# Recupera_ao_e_Paraquedas.net
KiCad netlist of a schematic drawn in EAGLE
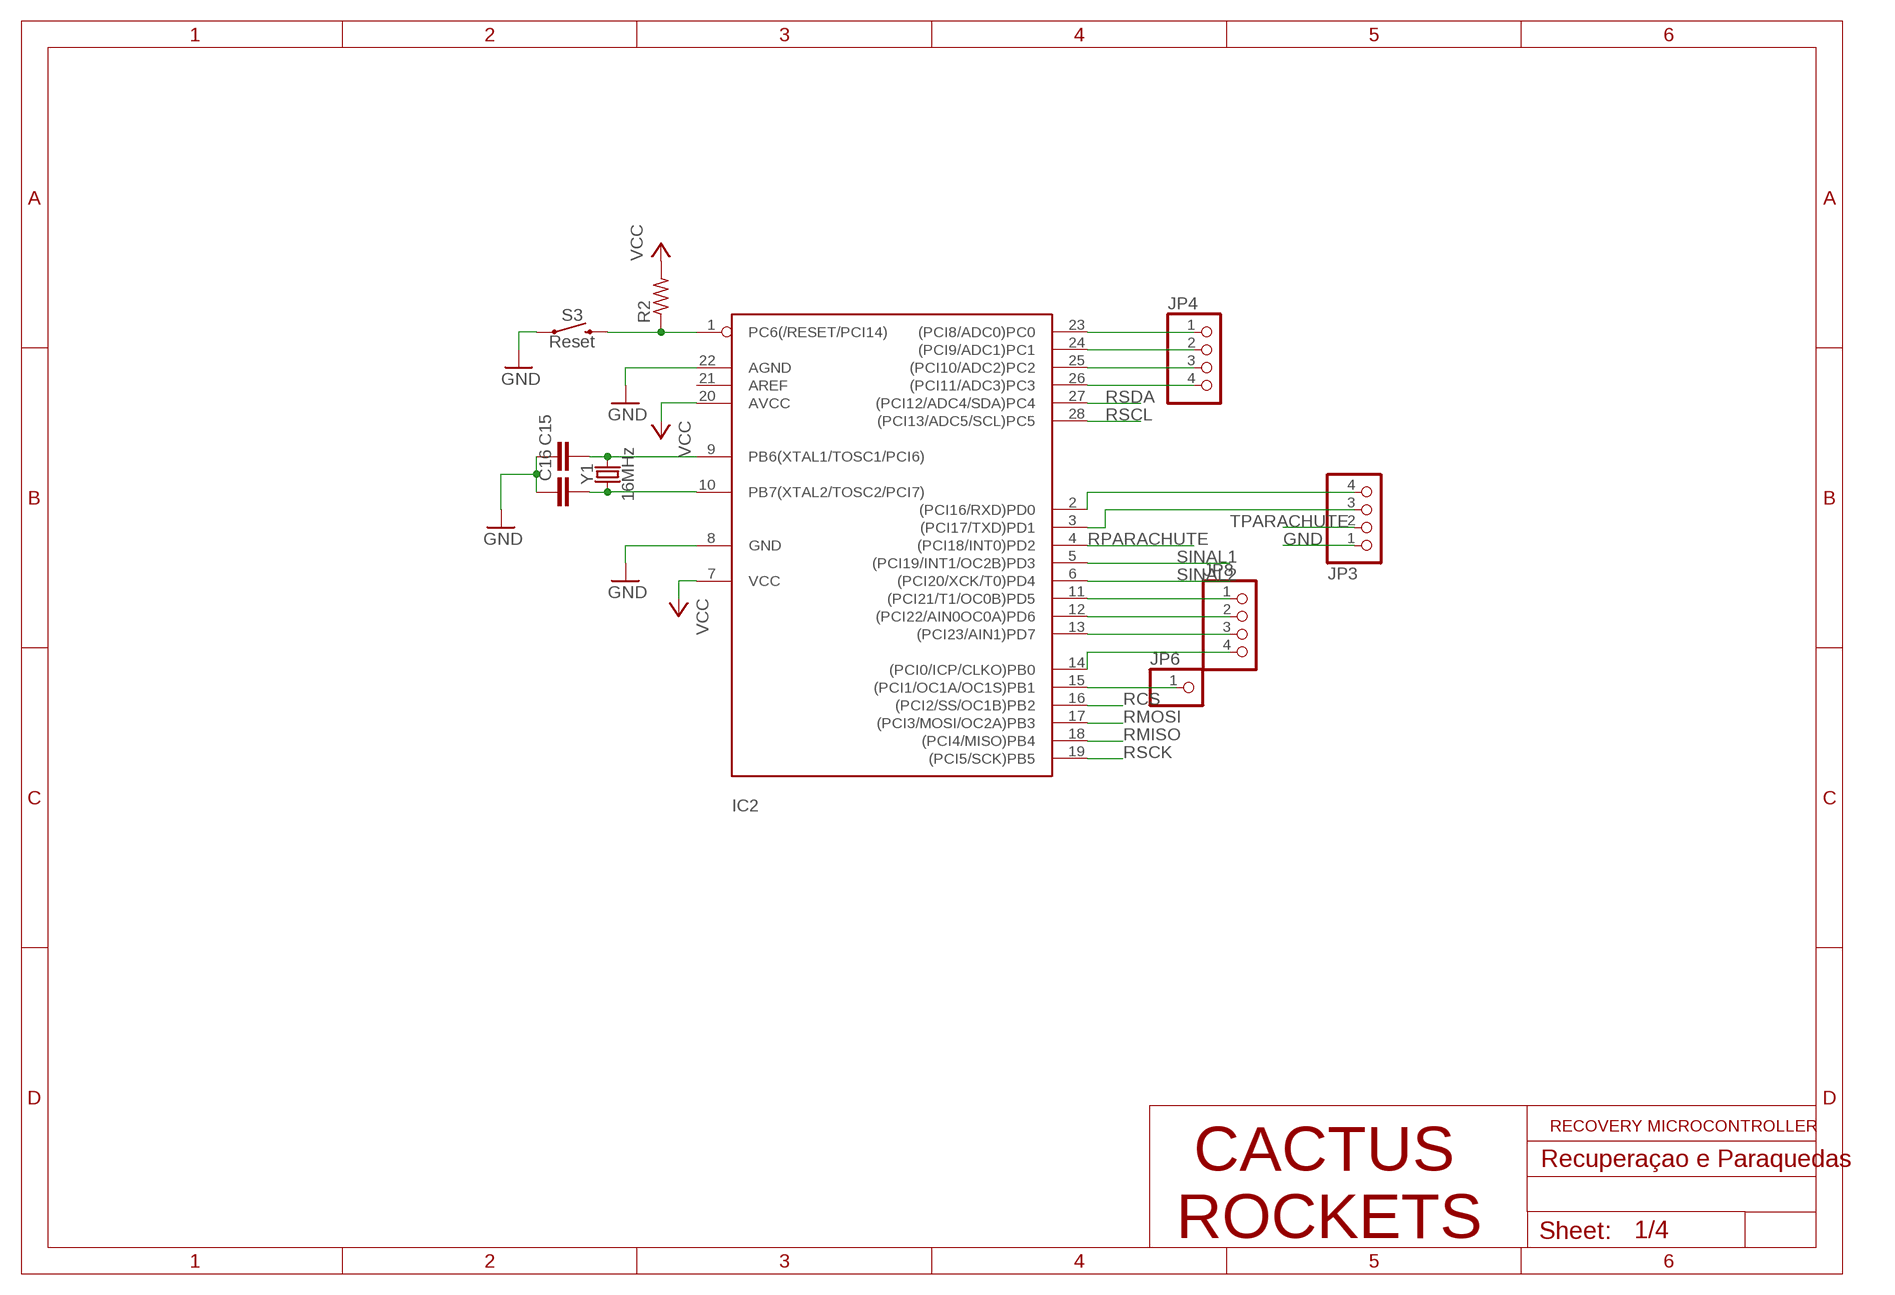
[diagram p0: schematic, sheet 1]
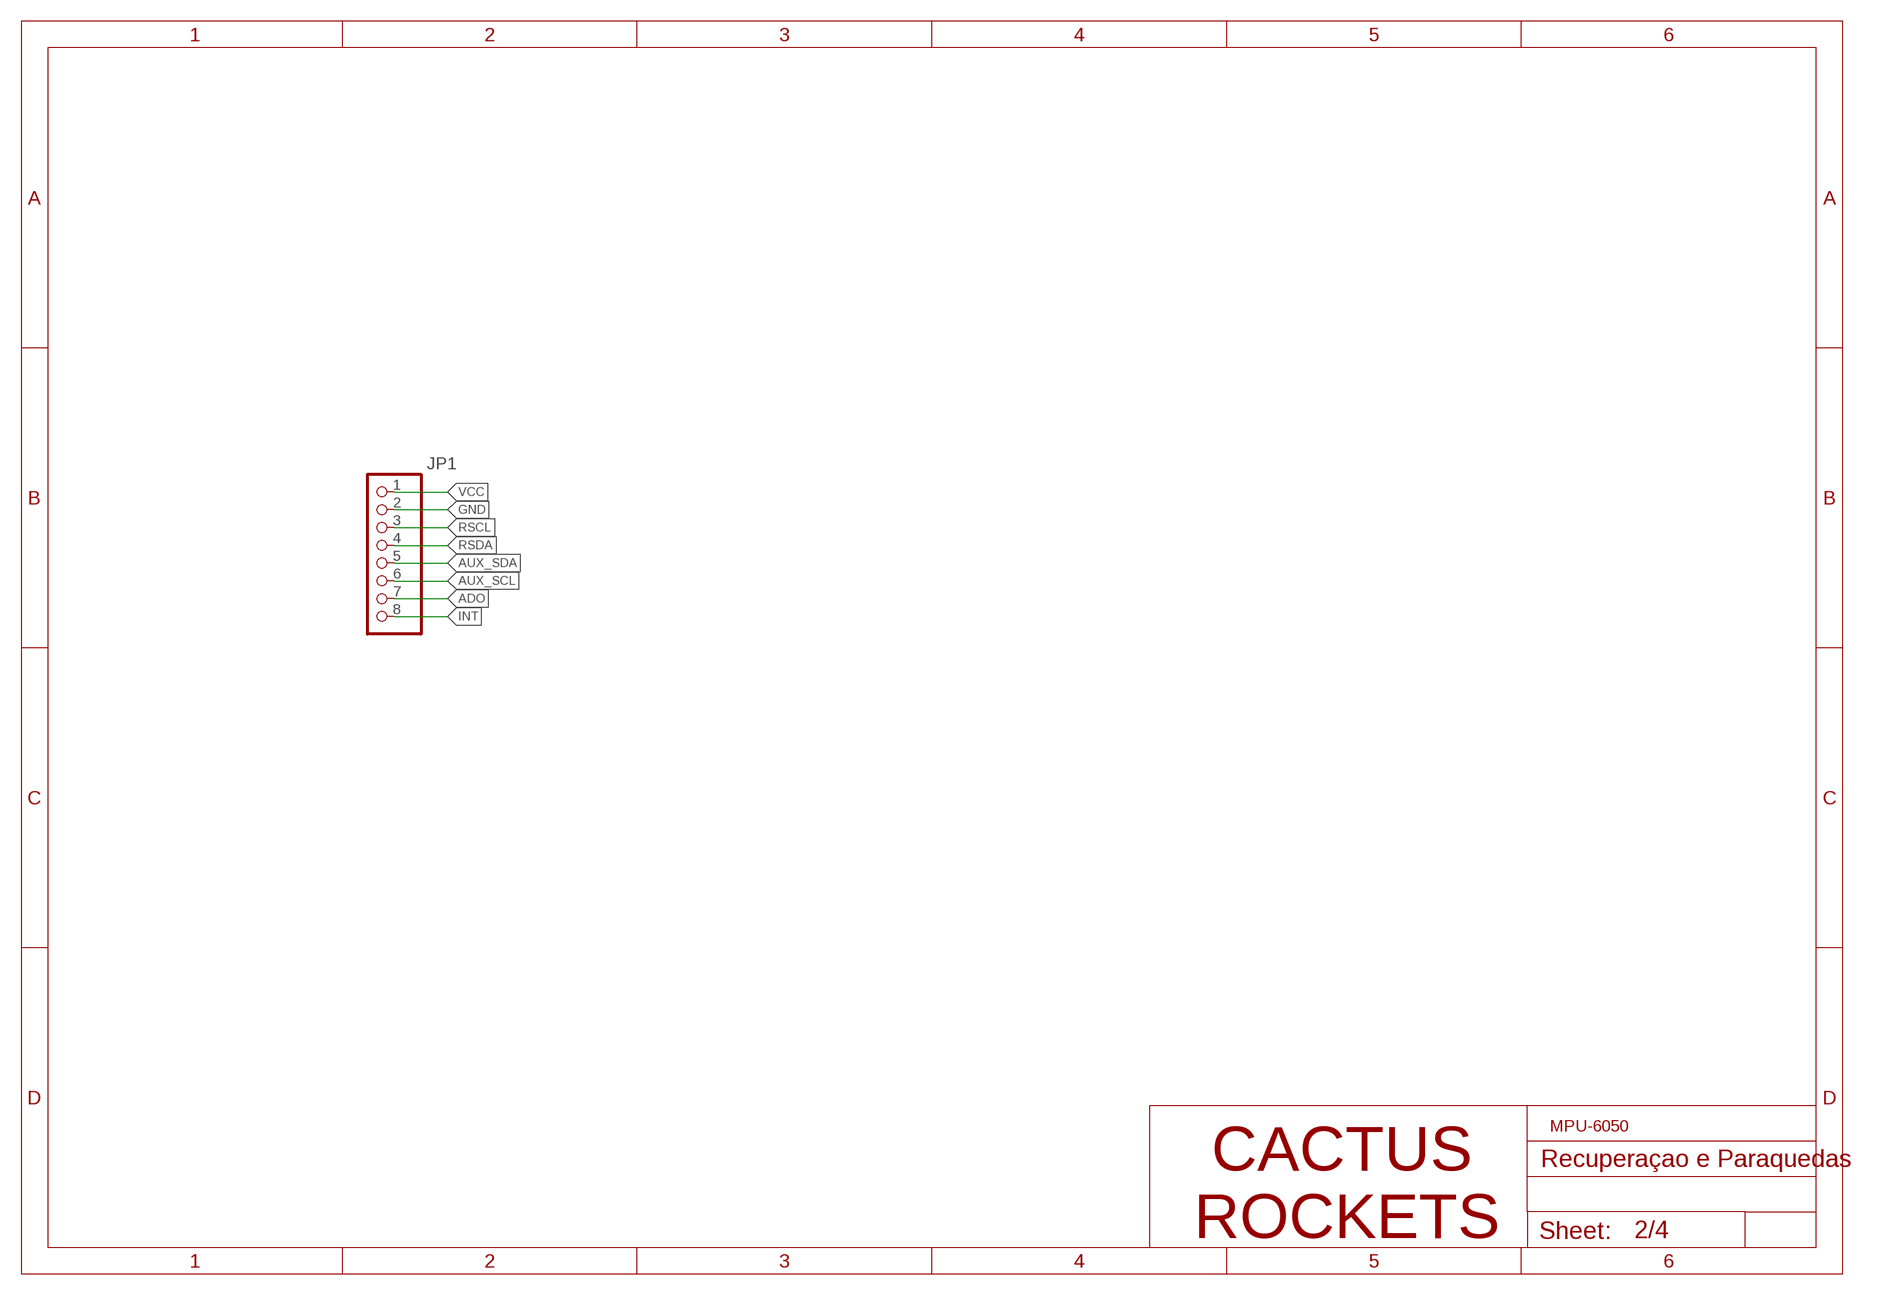
[diagram p1: schematic, sheet 2]
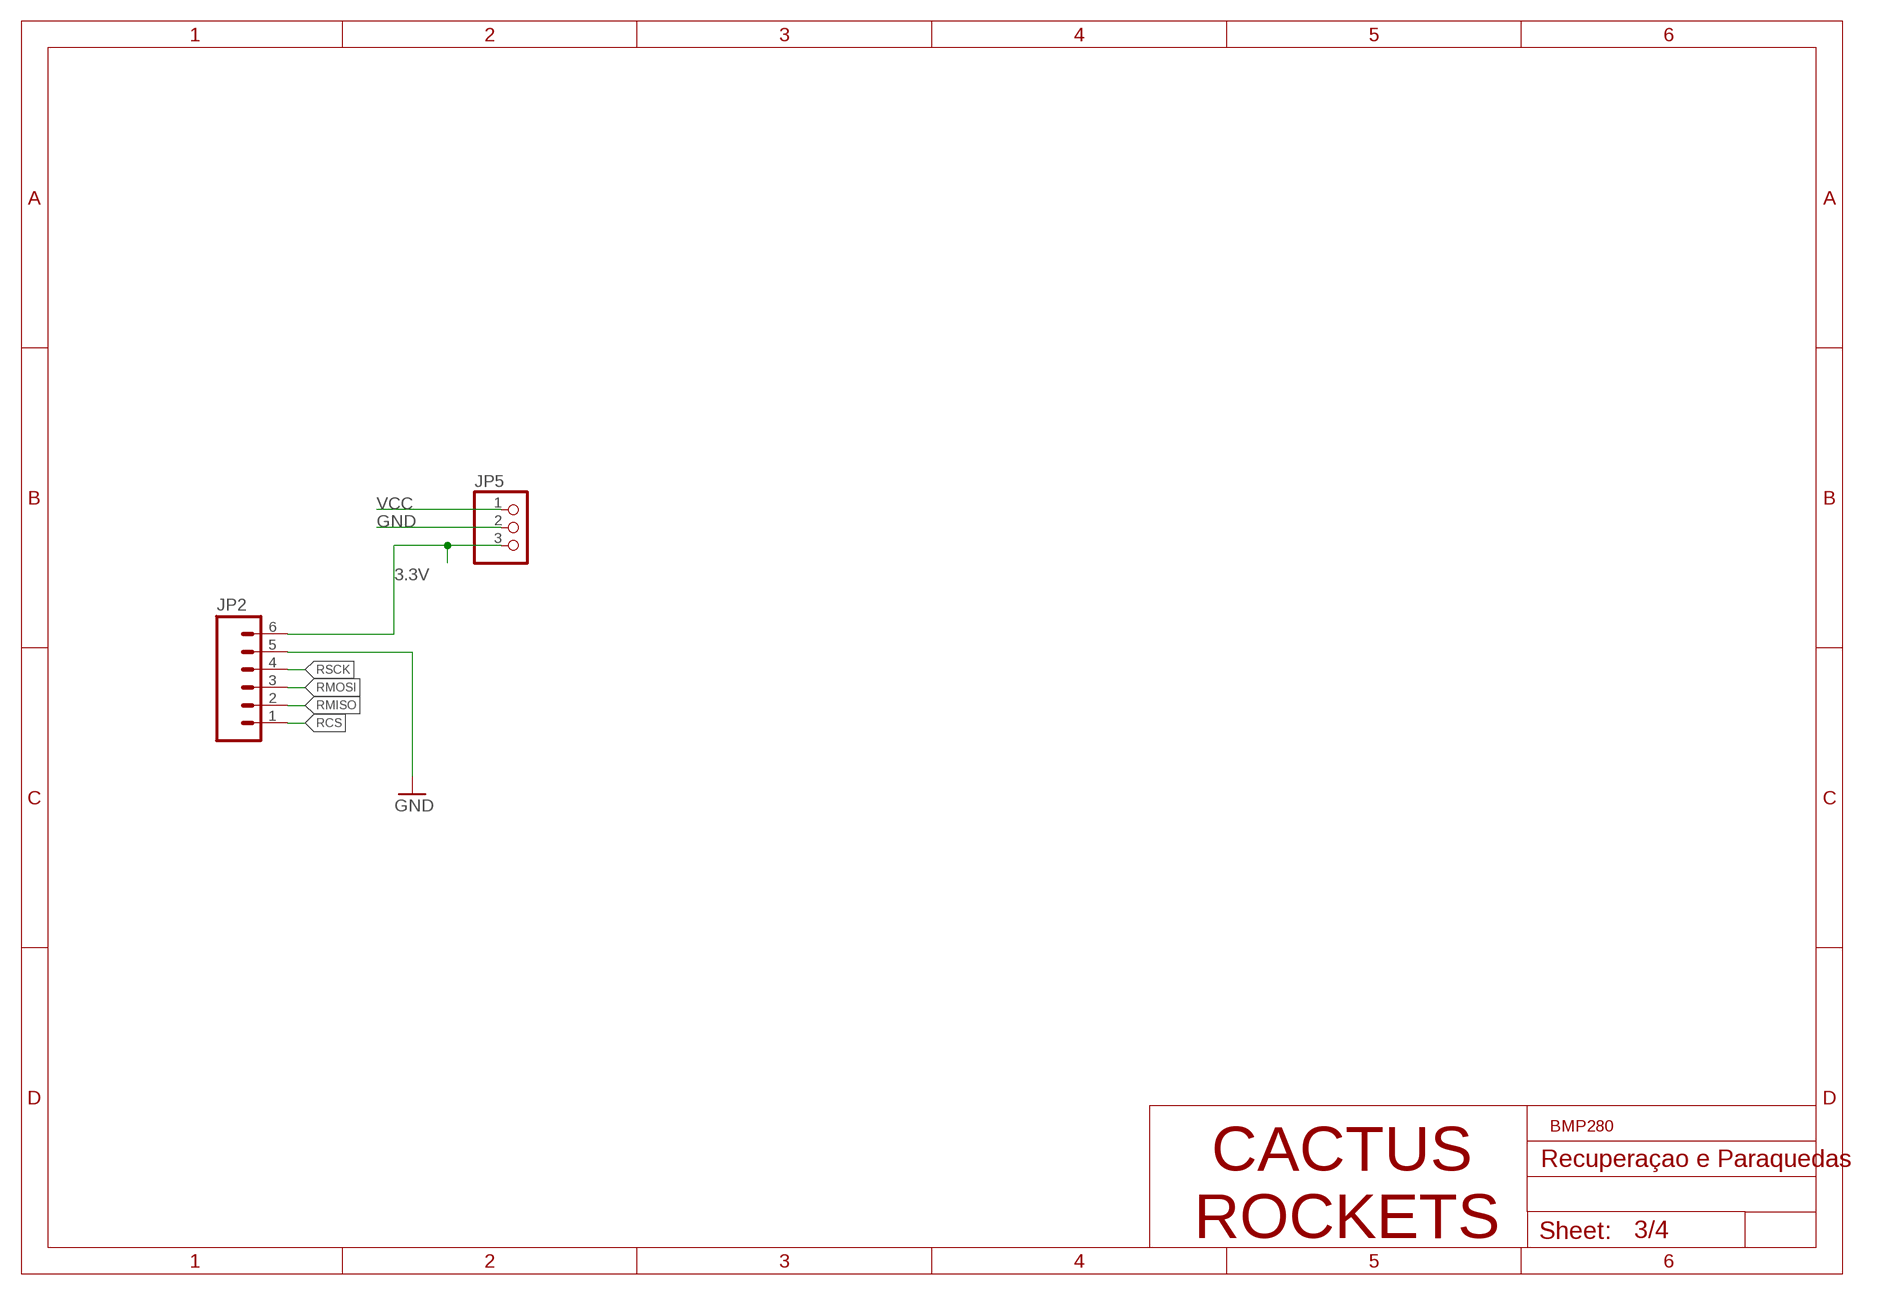
[diagram p2: schematic, sheet 3]
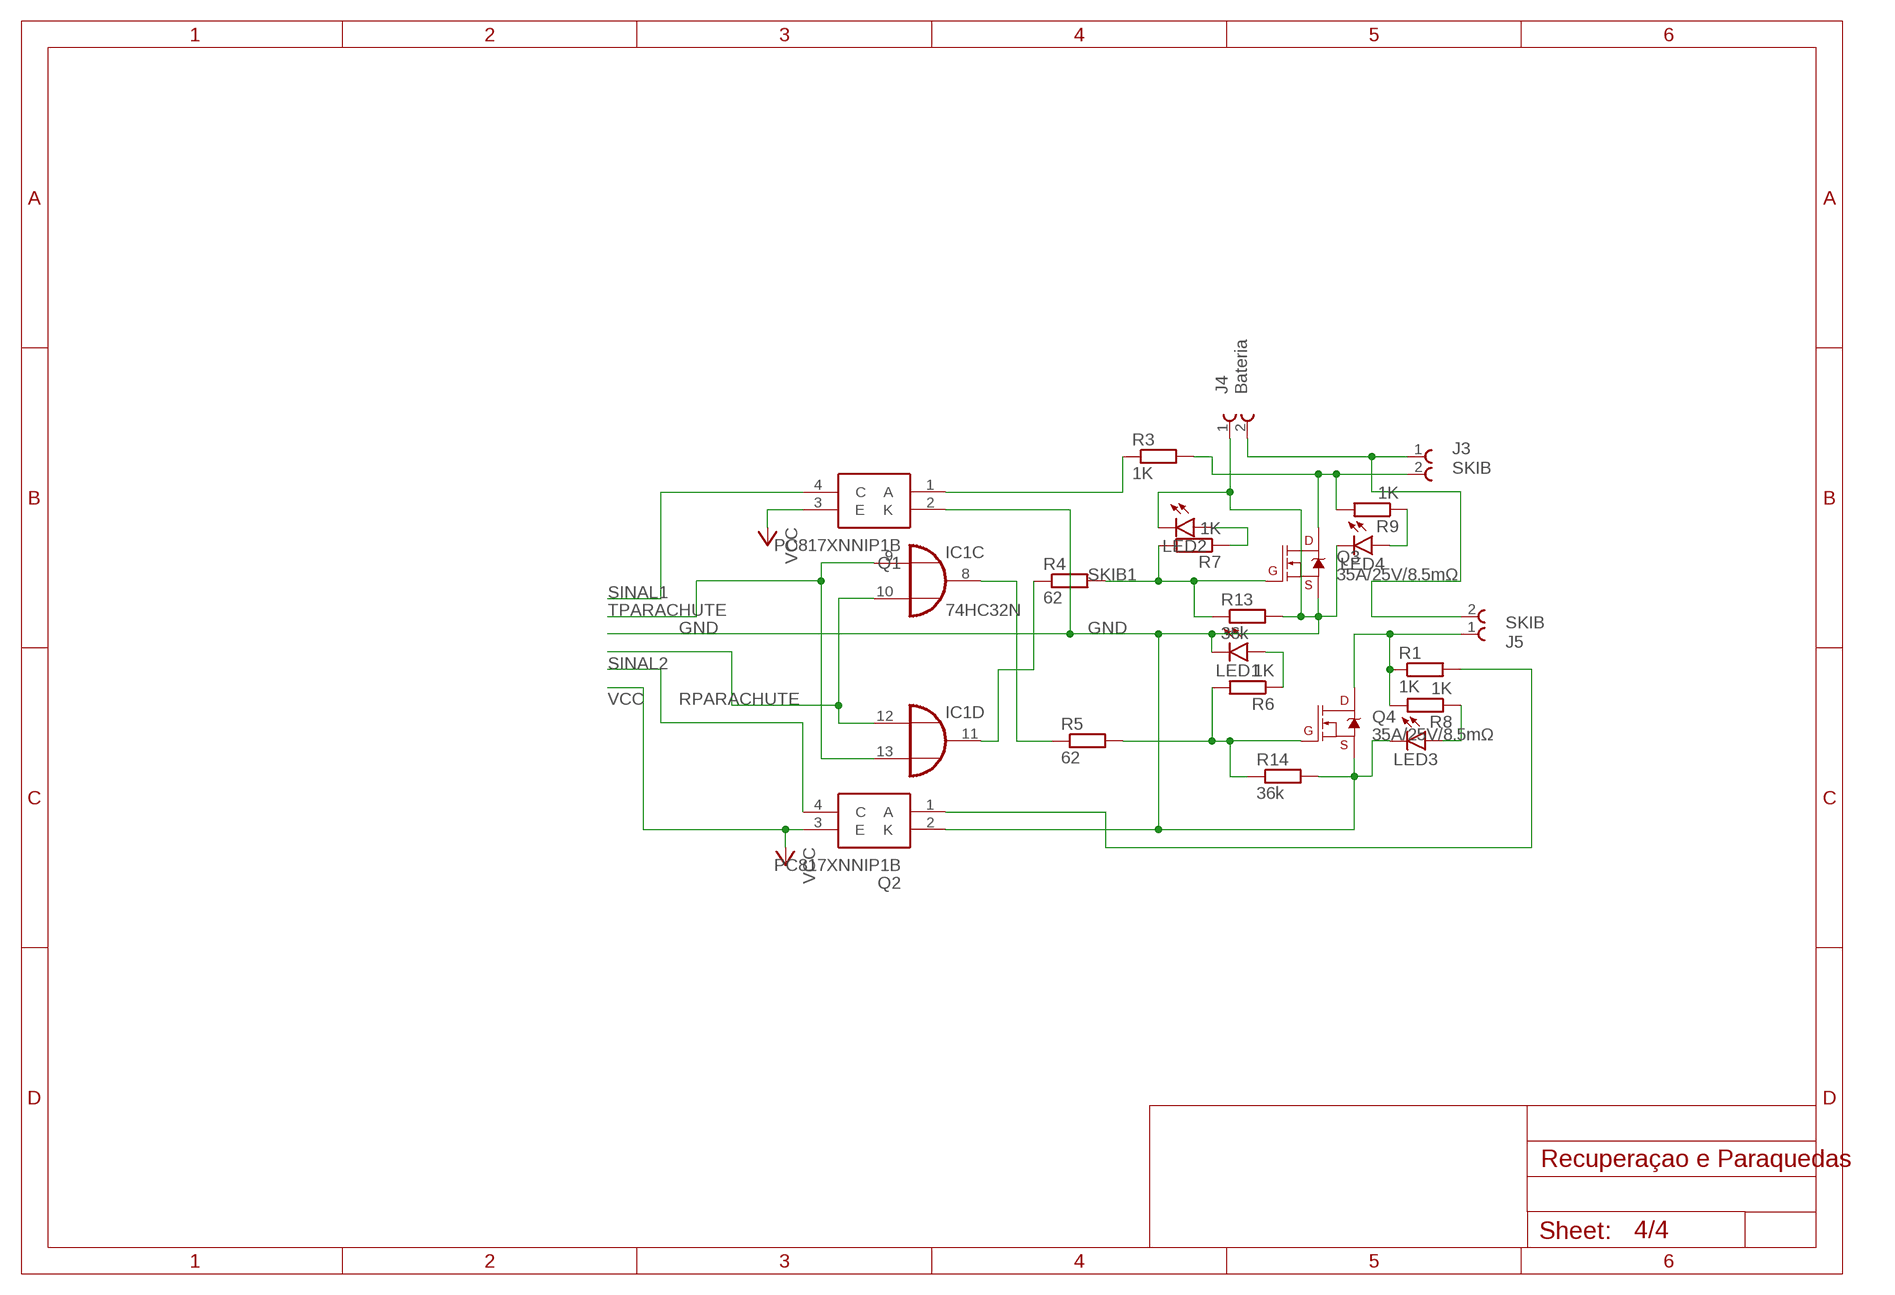
[diagram p3: schematic, sheet 4]

(export (version "E")
  (design (tool "Eeschema 10.0.6"))
  (components
    (comp (ref "JP1")
      (value "PINHD-1X8")
      (footprint "eagle-import:1X08")
      (libsource (lib "eagle-import") (part "PINHD-1X8"))
    )
    (comp (ref "JP2")
      (value "M06NO_SILK_FEMALE_PTH")
      (footprint "eagle-import:1X06_NO_SILK")
      (libsource (lib "eagle-import") (part "M06NO_SILK_FEMALE_PTH"))
    )
    (comp (ref "JP5")
      (value "PINHD-1X3/90")
      (footprint "eagle-import:1X03_90")
      (libsource (lib "eagle-import") (part "PINHD-1X3/90"))
    )
    (comp (ref "C15")
      (value "C-EU025-025X050")
      (footprint "eagle-import:C025-025X050")
      (libsource (lib "eagle-import") (part "C-EU025-025X050"))
    )
    (comp (ref "C16")
      (value "C-EU025-025X050")
      (footprint "eagle-import:C025-025X050")
      (libsource (lib "eagle-import") (part "C-EU025-025X050"))
    )
    (comp (ref "IC2")
      (value "ATMEGA328-20P")
      (footprint "eagle-import:DIL28-3")
      (libsource (lib "eagle-import") (part "ATMEGA328P-20"))
    )
    (comp (ref "JP3")
      (value "PINHD-1X4/90")
      (footprint "eagle-import:1X04_90")
      (libsource (lib "eagle-import") (part "PINHD-1X4/90"))
    )
    (comp (ref "JP4")
      (value "PINHD-1X4")
      (footprint "eagle-import:1X04")
      (libsource (lib "eagle-import") (part "PINHD-1X4"))
    )
    (comp (ref "JP6")
      (value "PINHD-1X1")
      (footprint "eagle-import:1X01")
      (libsource (lib "eagle-import") (part "PINHD-1X1"))
    )
    (comp (ref "JP8")
      (value "PINHD-1X4")
      (footprint "eagle-import:1X04")
      (libsource (lib "eagle-import") (part "PINHD-1X4"))
    )
    (comp (ref "R2")
      (value "R-US_0207/10")
      (footprint "eagle-import:0207_10")
      (libsource (lib "eagle-import") (part "R-US_0207/10"))
    )
    (comp (ref "S3")
      (value "Reset")
      (footprint "eagle-import:TACTILE_SWITCH_PTH_6.0MM")
      (libsource (lib "eagle-import") (part "MOMENTARY-SWITCH-SPST-PTH-6.0MM"))
    )
    (comp (ref "Y1")
      (value "16MHz")
      (footprint "eagle-import:HC49US")
      (libsource (lib "eagle-import") (part "CRYSTAL-16MHZPTH-HC49US"))
    )
    (comp (ref "IC1")
      (value "74HC32N")
      (footprint "eagle-import:DIL14")
      (libsource (lib "eagle-import") (part "7432NHC"))
    )
    (comp (ref "J3")
      (value "SKIB")
      (footprint "eagle-import:691111710002")
      (fields (field (name "MF") "Wurth Electronics") (field (name "MP") "691111710002"))
      (libsource (lib "eagle-import") (part "691111710002"))
    )
    (comp (ref "J4")
      (value "Bateria")
      (footprint "eagle-import:691111710002")
      (fields (field (name "MF") "Wurth Electronics") (field (name "MP") "691111710002"))
      (libsource (lib "eagle-import") (part "691111710002"))
    )
    (comp (ref "J5")
      (value "SKIB")
      (footprint "eagle-import:691111710002")
      (fields (field (name "MF") "Wurth Electronics") (field (name "MP") "691111710002"))
      (libsource (lib "eagle-import") (part "691111710002"))
    )
    (comp (ref "LED1")
      (value "LEDCHIP-LED0805")
      (footprint "eagle-import:CHIP-LED0805")
      (libsource (lib "eagle-import") (part "LEDCHIP-LED0805"))
    )
    (comp (ref "LED2")
      (value "LEDCHIP-LED0805")
      (footprint "eagle-import:CHIP-LED0805")
      (libsource (lib "eagle-import") (part "LEDCHIP-LED0805"))
    )
    (comp (ref "LED3")
      (value "LEDCHIP-LED0805")
      (footprint "eagle-import:CHIP-LED0805")
      (libsource (lib "eagle-import") (part "LEDCHIP-LED0805"))
    )
    (comp (ref "LED4")
      (value "LEDCHIP-LED0805")
      (footprint "eagle-import:CHIP-LED0805")
      (libsource (lib "eagle-import") (part "LEDCHIP-LED0805"))
    )
    (comp (ref "Q1")
      (value "PC817XNNIP1B")
      (footprint "eagle-import:SOP254P960X420-4N")
      (fields (field (name "MOUSER_PART_NUMBER") "852-PC817XNNIP1B"))
      (libsource (lib "eagle-import") (part "PC817XNNIP1B"))
    )
    (comp (ref "Q2")
      (value "PC817XNNIP1B")
      (footprint "eagle-import:SOP254P960X420-4N")
      (fields (field (name "MOUSER_PART_NUMBER") "852-PC817XNNIP1B"))
      (libsource (lib "eagle-import") (part "PC817XNNIP1B"))
    )
    (comp (ref "Q3")
      (value "35A/25V/8.5mΩ")
      (footprint "eagle-import:TO-252_DPAK")
      (libsource (lib "eagle-import") (part "MOSFET-NCH-FDD8780"))
    )
    (comp (ref "Q4")
      (value "35A/25V/8.5mΩ")
      (footprint "eagle-import:TO-252_DPAK")
      (libsource (lib "eagle-import") (part "MOSFET-NCH-FDD8780"))
    )
    (comp (ref "R1")
      (value "1K")
      (footprint "eagle-import:R0603")
      (libsource (lib "eagle-import") (part "R-EU_R0603"))
    )
    (comp (ref "R3")
      (value "1K")
      (footprint "eagle-import:R0603")
      (libsource (lib "eagle-import") (part "R-EU_R0603"))
    )
    (comp (ref "R4")
      (value "62")
      (footprint "eagle-import:M0805")
      (libsource (lib "eagle-import") (part "R-EU_M0805"))
    )
    (comp (ref "R5")
      (value "62")
      (footprint "eagle-import:M0805")
      (libsource (lib "eagle-import") (part "R-EU_M0805"))
    )
    (comp (ref "R6")
      (value "1K")
      (footprint "eagle-import:M0805")
      (libsource (lib "eagle-import") (part "R-EU_M0805"))
    )
    (comp (ref "R7")
      (value "1K")
      (footprint "eagle-import:M0805")
      (libsource (lib "eagle-import") (part "R-EU_M0805"))
    )
    (comp (ref "R8")
      (value "1K")
      (footprint "eagle-import:M0805")
      (libsource (lib "eagle-import") (part "R-EU_M0805"))
    )
    (comp (ref "R9")
      (value "1K")
      (footprint "eagle-import:M0805")
      (libsource (lib "eagle-import") (part "R-EU_M0805"))
    )
    (comp (ref "R13")
      (value "36k")
      (footprint "eagle-import:M0805")
      (libsource (lib "eagle-import") (part "R-EU_M0805"))
    )
    (comp (ref "R14")
      (value "36k")
      (footprint "eagle-import:M0805")
      (libsource (lib "eagle-import") (part "R-EU_M0805"))
    )
  )
  (nets
    (net (code "1") (name "3.3V") (class "Default")
      (node (ref "JP2") (pin "6") (pinfunction "6_6") (pintype "passive"))
      (node (ref "JP5") (pin "3") (pinfunction "3_3") (pintype "passive"))
    )
    (net (code "2") (name "ADO") (class "Default")
      (node (ref "JP1") (pin "7") (pinfunction "7_7") (pintype "passive"))
    )
    (net (code "3") (name "AUX_SCL") (class "Default")
      (node (ref "JP1") (pin "6") (pinfunction "6_6") (pintype "passive"))
    )
    (net (code "4") (name "AUX_SDA") (class "Default")
      (node (ref "JP1") (pin "5") (pinfunction "5_5") (pintype "passive"))
    )
    (net (code "5") (name "GND") (class "Default")
      (node (ref "C15") (pin "1") (pinfunction "1_1") (pintype "passive"))
      (node (ref "C16") (pin "1") (pinfunction "1_1") (pintype "passive"))
      (node (ref "IC2") (pin "22") (pinfunction "AGND_22") (pintype "bidirectional"))
      (node (ref "IC2") (pin "8") (pinfunction "GND_8") (pintype "bidirectional"))
      (node (ref "J4") (pin "1") (pinfunction "1_1") (pintype "passive"))
      (node (ref "JP1") (pin "2") (pinfunction "2_2") (pintype "passive"))
      (node (ref "JP2") (pin "5") (pinfunction "5_5") (pintype "passive"))
      (node (ref "JP3") (pin "1") (pinfunction "1_1") (pintype "passive"))
      (node (ref "JP5") (pin "2") (pinfunction "2_2") (pintype "passive"))
      (node (ref "LED1") (pin "C") (pinfunction "C_C") (pintype "passive"))
      (node (ref "LED2") (pin "C") (pinfunction "C_C") (pintype "passive"))
      (node (ref "LED3") (pin "C") (pinfunction "C_C") (pintype "passive"))
      (node (ref "LED4") (pin "C") (pinfunction "C_C") (pintype "passive"))
      (node (ref "Q1") (pin "2") (pinfunction "K_2") (pintype "bidirectional"))
      (node (ref "Q2") (pin "2") (pinfunction "K_2") (pintype "bidirectional"))
      (node (ref "Q3") (pin "3") (pinfunction "S_3") (pintype "bidirectional"))
      (node (ref "Q4") (pin "3") (pinfunction "S_3") (pintype "bidirectional"))
      (node (ref "R13") (pin "2") (pinfunction "2_2") (pintype "passive"))
      (node (ref "R14") (pin "2") (pinfunction "2_2") (pintype "passive"))
      (node (ref "S3") (pin "1") (pinfunction "1_1") (pintype "passive"))
      (node (ref "S3") (pin "2") (pinfunction "1_2") (pintype "passive"))
    )
    (net (code "6") (name "INT") (class "Default")
      (node (ref "JP1") (pin "8") (pinfunction "8_8") (pintype "passive"))
    )
    (net (code "7") (name "Net-(IC1C-O)") (class "Default")
      (node (ref "IC1") (pin "8") (pinfunction "O_8") (pintype "output"))
      (node (ref "R5") (pin "1") (pinfunction "1_1") (pintype "passive"))
    )
    (net (code "8") (name "Net-(IC1D-O)") (class "Default")
      (node (ref "IC1") (pin "11") (pinfunction "O_11") (pintype "output"))
      (node (ref "R4") (pin "1") (pinfunction "1_1") (pintype "passive"))
    )
    (net (code "9") (name "Net-(IC2-(PCI0{slash}ICP{slash}CLKO)PB0)") (class "Default")
      (node (ref "IC2") (pin "14") (pinfunction "(PCI0/ICP/CLKO)PB0_14") (pintype "bidirectional"))
      (node (ref "JP8") (pin "4") (pinfunction "4_4") (pintype "passive"))
    )
    (net (code "10") (name "Net-(IC2-(PCI1{slash}OC1A{slash}OC1S)PB1)") (class "Default")
      (node (ref "IC2") (pin "15") (pinfunction "(PCI1/OC1A/OC1S)PB1_15") (pintype "bidirectional"))
      (node (ref "JP6") (pin "1") (pinfunction "1_1") (pintype "passive"))
    )
    (net (code "11") (name "Net-(IC2-(PCI8{slash}ADC0)PC0)") (class "Default")
      (node (ref "IC2") (pin "23") (pinfunction "(PCI8/ADC0)PC0_23") (pintype "bidirectional"))
      (node (ref "JP4") (pin "1") (pinfunction "1_1") (pintype "passive"))
    )
    (net (code "12") (name "Net-(IC2-(PCI9{slash}ADC1)PC1)") (class "Default")
      (node (ref "IC2") (pin "24") (pinfunction "(PCI9/ADC1)PC1_24") (pintype "bidirectional"))
      (node (ref "JP4") (pin "2") (pinfunction "2_2") (pintype "passive"))
    )
    (net (code "13") (name "Net-(IC2-(PCI10{slash}ADC2)PC2)") (class "Default")
      (node (ref "IC2") (pin "25") (pinfunction "(PCI10/ADC2)PC2_25") (pintype "bidirectional"))
      (node (ref "JP4") (pin "3") (pinfunction "3_3") (pintype "passive"))
    )
    (net (code "14") (name "Net-(IC2-(PCI11{slash}ADC3)PC3)") (class "Default")
      (node (ref "IC2") (pin "26") (pinfunction "(PCI11/ADC3)PC3_26") (pintype "bidirectional"))
      (node (ref "JP4") (pin "4") (pinfunction "4_4") (pintype "passive"))
    )
    (net (code "15") (name "Net-(IC2-(PCI16{slash}RXD)PD0)") (class "Default")
      (node (ref "IC2") (pin "2") (pinfunction "(PCI16/RXD)PD0_2") (pintype "bidirectional"))
      (node (ref "JP3") (pin "4") (pinfunction "4_4") (pintype "passive"))
    )
    (net (code "16") (name "Net-(IC2-(PCI17{slash}TXD)PD1)") (class "Default")
      (node (ref "IC2") (pin "3") (pinfunction "(PCI17/TXD)PD1_3") (pintype "bidirectional"))
      (node (ref "JP3") (pin "3") (pinfunction "3_3") (pintype "passive"))
    )
    (net (code "17") (name "Net-(IC2-(PCI21{slash}T1{slash}OC0B)PD5)") (class "Default")
      (node (ref "IC2") (pin "11") (pinfunction "(PCI21/T1/OC0B)PD5_11") (pintype "bidirectional"))
      (node (ref "JP8") (pin "1") (pinfunction "1_1") (pintype "passive"))
    )
    (net (code "18") (name "Net-(IC2-(PCI22{slash}AIN0OC0A)PD6)") (class "Default")
      (node (ref "IC2") (pin "12") (pinfunction "(PCI22/AIN0OC0A)PD6_12") (pintype "bidirectional"))
      (node (ref "JP8") (pin "2") (pinfunction "2_2") (pintype "passive"))
    )
    (net (code "19") (name "Net-(IC2-(PCI23{slash}AIN1)PD7)") (class "Default")
      (node (ref "IC2") (pin "13") (pinfunction "(PCI23/AIN1)PD7_13") (pintype "bidirectional"))
      (node (ref "JP8") (pin "3") (pinfunction "3_3") (pintype "passive"))
    )
    (net (code "20") (name "Net-(IC2-PB6(XTAL1{slash}TOSC1{slash}PCI6))") (class "Default")
      (node (ref "C15") (pin "2") (pinfunction "2_2") (pintype "passive"))
      (node (ref "IC2") (pin "9") (pinfunction "PB6(XTAL1/TOSC1/PCI6)_9") (pintype "bidirectional"))
      (node (ref "Y1") (pin "2") (pinfunction "2_2") (pintype "passive"))
    )
    (net (code "21") (name "Net-(IC2-PB7(XTAL2{slash}TOSC2{slash}PCI7))") (class "Default")
      (node (ref "C16") (pin "2") (pinfunction "2_2") (pintype "passive"))
      (node (ref "IC2") (pin "10") (pinfunction "PB7(XTAL2/TOSC2/PCI7)_10") (pintype "bidirectional"))
      (node (ref "Y1") (pin "1") (pinfunction "1_1") (pintype "passive"))
    )
    (net (code "22") (name "Net-(IC2-PC6({slash}RESET{slash}PCI14))") (class "Default")
      (node (ref "IC2") (pin "1") (pinfunction "PC6(/RESET/PCI14)_1") (pintype "bidirectional"))
      (node (ref "R2") (pin "1") (pinfunction "1_1") (pintype "passive"))
      (node (ref "S3") (pin "3") (pinfunction "2_3") (pintype "passive"))
      (node (ref "S3") (pin "4") (pinfunction "2_4") (pintype "passive"))
    )
    (net (code "23") (name "Net-(J3-Pad1)") (class "Default")
      (node (ref "J3") (pin "1") (pinfunction "1_1") (pintype "passive"))
      (node (ref "J4") (pin "2") (pinfunction "2_2") (pintype "passive"))
      (node (ref "J5") (pin "2") (pinfunction "2_2") (pintype "passive"))
    )
    (net (code "24") (name "Net-(LED1-PadA)") (class "Default")
      (node (ref "LED1") (pin "A") (pinfunction "A_A") (pintype "passive"))
      (node (ref "R6") (pin "1") (pinfunction "1_1") (pintype "passive"))
    )
    (net (code "25") (name "Net-(LED2-PadA)") (class "Default")
      (node (ref "LED2") (pin "A") (pinfunction "A_A") (pintype "passive"))
      (node (ref "R7") (pin "1") (pinfunction "1_1") (pintype "passive"))
    )
    (net (code "26") (name "Net-(LED3-PadA)") (class "Default")
      (node (ref "LED3") (pin "A") (pinfunction "A_A") (pintype "passive"))
      (node (ref "R8") (pin "1") (pinfunction "1_1") (pintype "passive"))
    )
    (net (code "27") (name "Net-(LED4-PadA)") (class "Default")
      (node (ref "LED4") (pin "A") (pinfunction "A_A") (pintype "passive"))
      (node (ref "R9") (pin "1") (pinfunction "1_1") (pintype "passive"))
    )
    (net (code "28") (name "Net-(Q1-A)") (class "Default")
      (node (ref "Q1") (pin "1") (pinfunction "A_1") (pintype "bidirectional"))
      (node (ref "R3") (pin "1") (pinfunction "1_1") (pintype "passive"))
    )
    (net (code "29") (name "Net-(Q2-A)") (class "Default")
      (node (ref "Q2") (pin "1") (pinfunction "A_1") (pintype "bidirectional"))
      (node (ref "R1") (pin "2") (pinfunction "2_2") (pintype "passive"))
    )
    (net (code "30") (name "Net-(Q3-D)") (class "Default")
      (node (ref "J3") (pin "2") (pinfunction "2_2") (pintype "passive"))
      (node (ref "Q3") (pin "2") (pinfunction "D_2") (pintype "bidirectional"))
      (node (ref "R3") (pin "2") (pinfunction "2_2") (pintype "passive"))
      (node (ref "R9") (pin "2") (pinfunction "2_2") (pintype "passive"))
    )
    (net (code "31") (name "Net-(Q4-D)") (class "Default")
      (node (ref "J5") (pin "1") (pinfunction "1_1") (pintype "passive"))
      (node (ref "Q4") (pin "2") (pinfunction "D_2") (pintype "bidirectional"))
      (node (ref "R1") (pin "1") (pinfunction "1_1") (pintype "passive"))
      (node (ref "R8") (pin "2") (pinfunction "2_2") (pintype "passive"))
    )
    (net (code "32") (name "Net-(Q4-G)") (class "Default")
      (node (ref "Q4") (pin "1") (pinfunction "G_1") (pintype "bidirectional"))
      (node (ref "R14") (pin "1") (pinfunction "1_1") (pintype "passive"))
      (node (ref "R5") (pin "2") (pinfunction "2_2") (pintype "passive"))
      (node (ref "R6") (pin "2") (pinfunction "2_2") (pintype "passive"))
    )
    (net (code "33") (name "RCS") (class "Default")
      (node (ref "IC2") (pin "16") (pinfunction "(PCI2/SS/OC1B)PB2_16") (pintype "bidirectional"))
      (node (ref "JP2") (pin "1") (pinfunction "1_1") (pintype "passive"))
    )
    (net (code "34") (name "RMISO") (class "Default")
      (node (ref "IC2") (pin "18") (pinfunction "(PCI4/MISO)PB4_18") (pintype "bidirectional"))
      (node (ref "JP2") (pin "2") (pinfunction "2_2") (pintype "passive"))
    )
    (net (code "35") (name "RMOSI") (class "Default")
      (node (ref "IC2") (pin "17") (pinfunction "(PCI3/MOSI/OC2A)PB3_17") (pintype "bidirectional"))
      (node (ref "JP2") (pin "3") (pinfunction "3_3") (pintype "passive"))
    )
    (net (code "36") (name "RPARACHUTE") (class "Default")
      (node (ref "IC1") (pin "10") (pinfunction "I1_10") (pintype "input"))
      (node (ref "IC1") (pin "12") (pinfunction "I0_12") (pintype "input"))
      (node (ref "IC2") (pin "4") (pinfunction "(PCI18/INT0)PD2_4") (pintype "bidirectional"))
    )
    (net (code "37") (name "RSCK") (class "Default")
      (node (ref "IC2") (pin "19") (pinfunction "(PCI5/SCK)PB5_19") (pintype "bidirectional"))
      (node (ref "JP2") (pin "4") (pinfunction "4_4") (pintype "passive"))
    )
    (net (code "38") (name "RSCL") (class "Default")
      (node (ref "IC2") (pin "28") (pinfunction "(PCI13/ADC5/SCL)PC5_28") (pintype "bidirectional"))
      (node (ref "JP1") (pin "3") (pinfunction "3_3") (pintype "passive"))
    )
    (net (code "39") (name "RSDA") (class "Default")
      (node (ref "IC2") (pin "27") (pinfunction "(PCI12/ADC4/SDA)PC4_27") (pintype "bidirectional"))
      (node (ref "JP1") (pin "4") (pinfunction "4_4") (pintype "passive"))
    )
    (net (code "40") (name "SINAL1") (class "Default")
      (node (ref "IC2") (pin "5") (pinfunction "(PCI19/INT1/OC2B)PD3_5") (pintype "bidirectional"))
      (node (ref "Q1") (pin "4") (pinfunction "C_4") (pintype "bidirectional"))
    )
    (net (code "41") (name "SINAL2") (class "Default")
      (node (ref "IC2") (pin "6") (pinfunction "(PCI20/XCK/T0)PD4_6") (pintype "bidirectional"))
      (node (ref "Q2") (pin "4") (pinfunction "C_4") (pintype "bidirectional"))
    )
    (net (code "42") (name "SKIB1") (class "Default")
      (node (ref "Q3") (pin "1") (pinfunction "G_1") (pintype "bidirectional"))
      (node (ref "R13") (pin "1") (pinfunction "1_1") (pintype "passive"))
      (node (ref "R4") (pin "2") (pinfunction "2_2") (pintype "passive"))
      (node (ref "R7") (pin "2") (pinfunction "2_2") (pintype "passive"))
    )
    (net (code "43") (name "TPARACHUTE") (class "Default")
      (node (ref "IC1") (pin "13") (pinfunction "I1_13") (pintype "input"))
      (node (ref "IC1") (pin "9") (pinfunction "I0_9") (pintype "input"))
      (node (ref "JP3") (pin "2") (pinfunction "2_2") (pintype "passive"))
    )
    (net (code "44") (name "VCC") (class "Default")
      (node (ref "IC2") (pin "20") (pinfunction "AVCC_20") (pintype "bidirectional"))
      (node (ref "IC2") (pin "7") (pinfunction "VCC_7") (pintype "bidirectional"))
      (node (ref "JP1") (pin "1") (pinfunction "1_1") (pintype "passive"))
      (node (ref "JP5") (pin "1") (pinfunction "1_1") (pintype "passive"))
      (node (ref "Q1") (pin "3") (pinfunction "E_3") (pintype "bidirectional"))
      (node (ref "Q2") (pin "3") (pinfunction "E_3") (pintype "bidirectional"))
      (node (ref "R2") (pin "2") (pinfunction "2_2") (pintype "passive"))
    )
    (net (code "45") (name "unconnected-(IC2-AREF-Pad21)") (class "Default")
      (node (ref "IC2") (pin "21") (pinfunction "AREF_21") (pintype "bidirectional"))
    )
  )
)
